# ArduIRv2.net
KiCad netlist of a schematic drawn in EAGLE
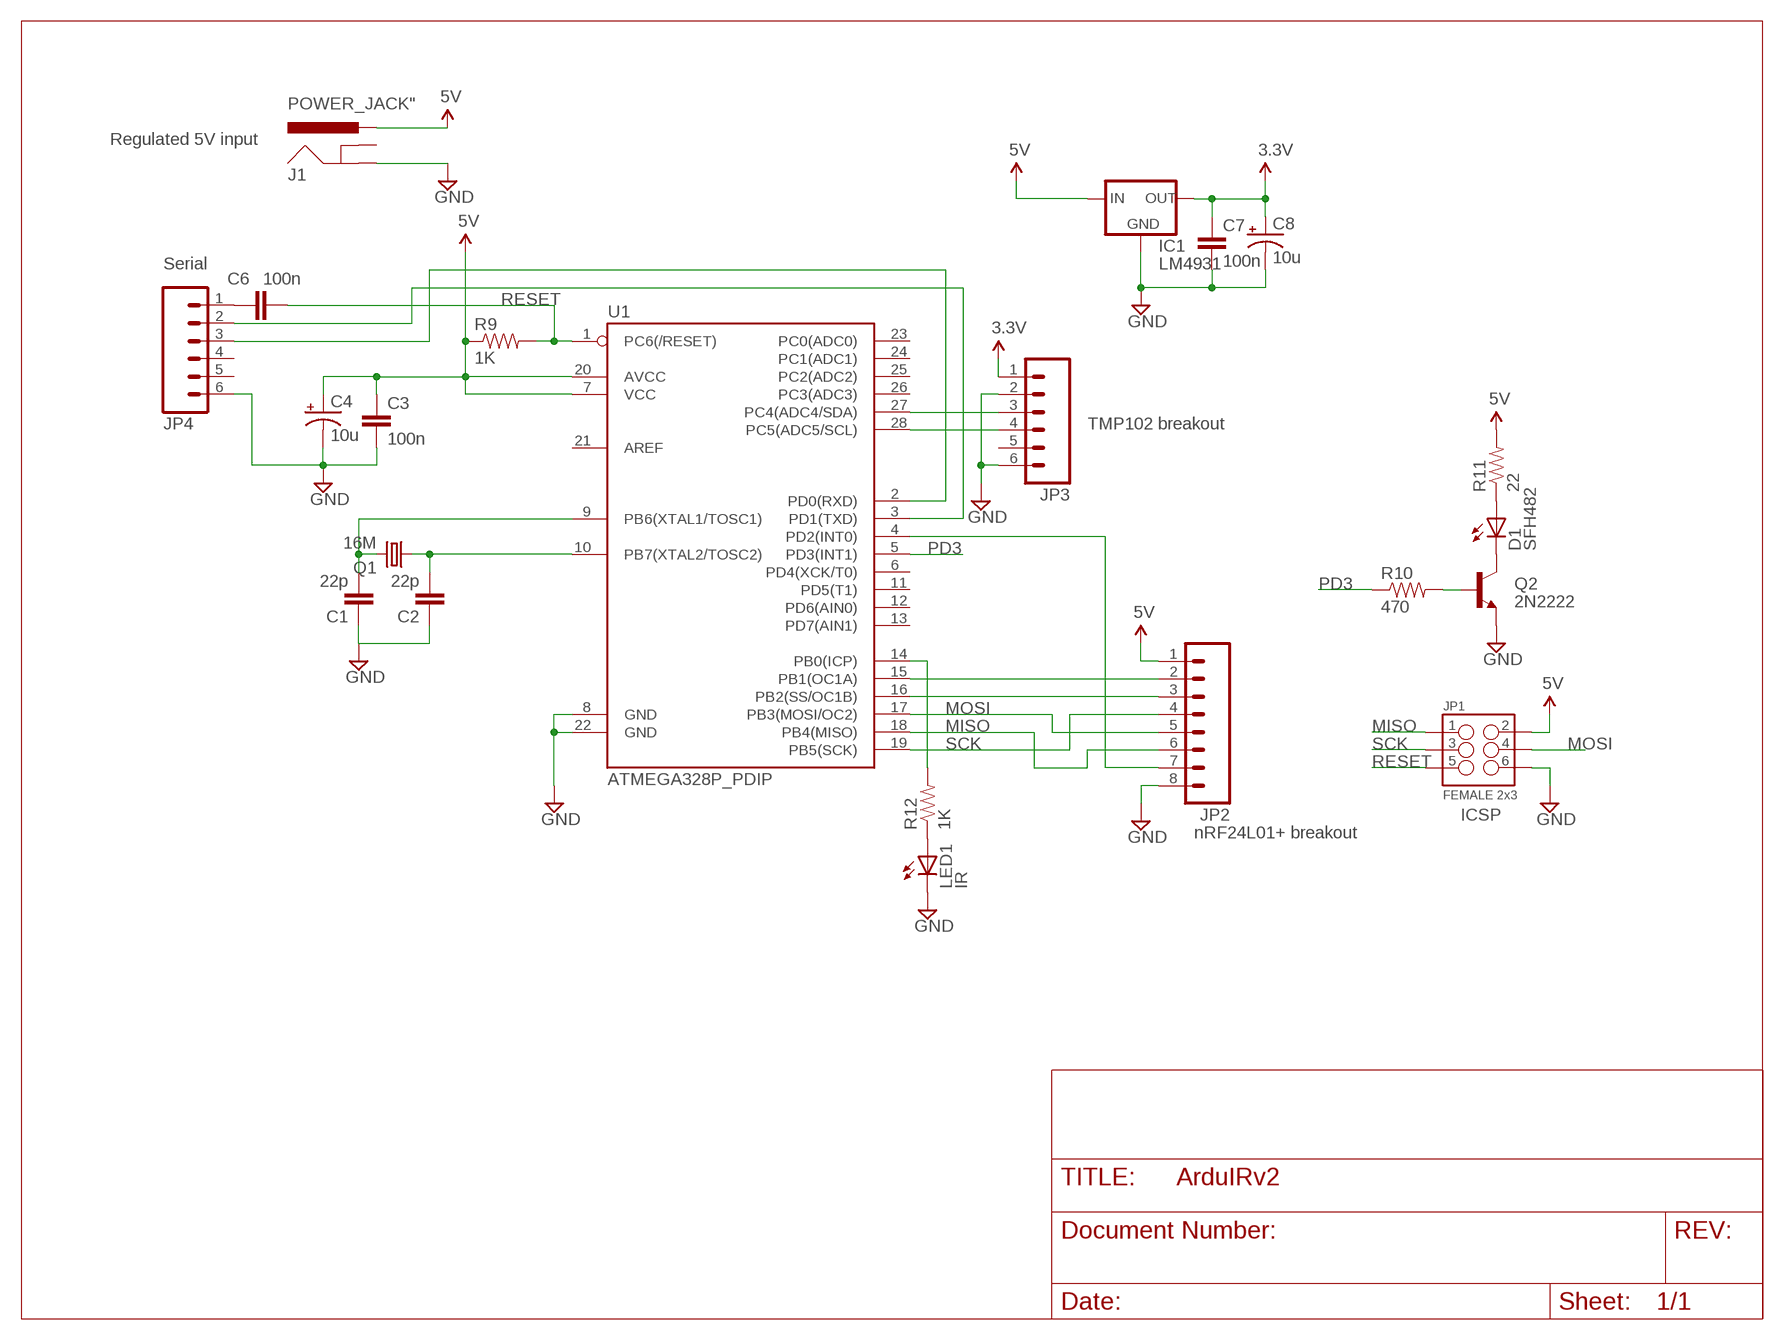
[diagram p0: schematic, sheet 1]

(export (version "E")
  (design (tool "Eeschema 10.0.6"))
  (components
    (comp (ref "C1")
      (value "22p")
      (footprint "eagle-import:CAP-PTH-SMALL")
      (libsource (lib "eagle-import") (part "CAPPTH"))
    )
    (comp (ref "C2")
      (value "22p")
      (footprint "eagle-import:CAP-PTH-SMALL")
      (libsource (lib "eagle-import") (part "CAPPTH"))
    )
    (comp (ref "C3")
      (value "100n")
      (footprint "eagle-import:CAP-PTH-SMALL-KIT")
      (libsource (lib "eagle-import") (part "0.1UF-50V-20%(PTH)KIT-EZ"))
    )
    (comp (ref "C4")
      (value "10u")
      (footprint "eagle-import:CPOL-RADIAL-10UF-25V")
      (libsource (lib "eagle-import") (part "CAP_POLPTH2"))
    )
    (comp (ref "C6")
      (value "100n")
      (footprint "eagle-import:CAP-PTH-SMALL-KIT")
      (libsource (lib "eagle-import") (part "0.1UF-50V-20%(PTH)KIT-EZ"))
    )
    (comp (ref "C7")
      (value "100n")
      (footprint "eagle-import:CAP-PTH-SMALL-KIT")
      (libsource (lib "eagle-import") (part "0.1UF-50V-20%(PTH)KIT-EZ"))
    )
    (comp (ref "C8")
      (value "10u")
      (footprint "eagle-import:CPOL-RADIAL-10UF-25V")
      (libsource (lib "eagle-import") (part "CAP_POLPTH2"))
    )
    (comp (ref "D1")
      (value "SFH482")
      (footprint "eagle-import:SFH482")
      (libsource (lib "eagle-import") (part "SFH482"))
    )
    (comp (ref "IC1")
      (value "LM4931")
      (footprint "eagle-import:L4931_REGULATOR")
      (libsource (lib "eagle-import") (part "REGULATORTO220"))
    )
    (comp (ref "J1")
      (value "POWER_JACK\"")
      (footprint "eagle-import:POWER_JACK")
      (libsource (lib "eagle-import") (part "POWER_JACK{dblquote}"))
    )
    (comp (ref "JP1")
      (value "FEMALE 2x3")
      (footprint "eagle-import:2X3-SHROUDED")
      (libsource (lib "eagle-import") (part "M03X2SHROUD"))
    )
    (comp (ref "JP2")
      (value "M08SILK_FEMALE_PTH")
      (footprint "eagle-import:1X08")
      (libsource (lib "eagle-import") (part "M08SILK_FEMALE_PTH"))
    )
    (comp (ref "JP3")
      (value "M06SILK_FEMALE_PTH")
      (footprint "eagle-import:1X06")
      (libsource (lib "eagle-import") (part "M06SILK_FEMALE_PTH"))
    )
    (comp (ref "JP4")
      (value "M06SILK_FEMALE_PTH")
      (footprint "eagle-import:1X06")
      (libsource (lib "eagle-import") (part "M06SILK_FEMALE_PTH"))
    )
    (comp (ref "LED1")
      (value "IR")
      (footprint "eagle-import:LED5MM")
      (libsource (lib "eagle-import") (part "LED5MM"))
    )
    (comp (ref "Q1")
      (value "16M")
      (footprint "eagle-import:HC49US")
      (libsource (lib "eagle-import") (part "CRYSTALHC49US"))
    )
    (comp (ref "Q2")
      (value "2N2222")
      (footprint "eagle-import:TO-92-AMMO")
      (libsource (lib "eagle-import") (part "TRANSISTOR_NPNTO-92-AMMO"))
    )
    (comp (ref "R9")
      (value "1K")
      (footprint "eagle-import:AXIAL-0.1EZ")
      (libsource (lib "eagle-import") (part "1KOHM-1/4W-1%(PTH)VERT-KIT"))
    )
    (comp (ref "R10")
      (value "470")
      (footprint "eagle-import:AXIAL-0.1EZ")
      (libsource (lib "eagle-import") (part "1KOHM-1/4W-1%(PTH)VERT-KIT"))
    )
    (comp (ref "R11")
      (value "22")
      (footprint "eagle-import:AXIAL-0.1EZ")
      (libsource (lib "eagle-import") (part "1KOHM-1/4W-1%(PTH)VERT-KIT"))
    )
    (comp (ref "R12")
      (value "1K")
      (footprint "eagle-import:AXIAL-0.1EZ")
      (libsource (lib "eagle-import") (part "10KOHM-1/4W-1%(PTH)VERT-KIT"))
    )
    (comp (ref "U1")
      (value "ATMEGA328P_PDIP")
      (footprint "eagle-import:DIL28-3")
      (libsource (lib "eagle-import") (part "ATMEGA328P_PDIP"))
    )
  )
  (nets
    (net (code "1") (name "/MISO") (class "Default")
      (node (ref "JP1") (pin "1") (pinfunction "1_1") (pintype "bidirectional"))
      (node (ref "JP2") (pin "6") (pinfunction "6_6") (pintype "passive"))
      (node (ref "U1") (pin "18") (pinfunction "PB4(MISO)_18") (pintype "bidirectional"))
    )
    (net (code "2") (name "/MOSI") (class "Default")
      (node (ref "JP1") (pin "4") (pinfunction "4_4") (pintype "bidirectional"))
      (node (ref "JP2") (pin "5") (pinfunction "5_5") (pintype "passive"))
      (node (ref "U1") (pin "17") (pinfunction "PB3(MOSI/OC2)_17") (pintype "bidirectional"))
    )
    (net (code "3") (name "/PD3") (class "Default")
      (node (ref "R10") (pin "P$1") (pinfunction "1_P$1") (pintype "passive"))
      (node (ref "U1") (pin "5") (pinfunction "PD3(INT1)_5") (pintype "bidirectional"))
    )
    (net (code "4") (name "/RESET") (class "Default")
      (node (ref "C6") (pin "1") (pinfunction "1_1") (pintype "passive"))
      (node (ref "JP1") (pin "5") (pinfunction "5_5") (pintype "bidirectional"))
      (node (ref "R9") (pin "P$2") (pinfunction "2_P$2") (pintype "passive"))
      (node (ref "U1") (pin "1") (pinfunction "PC6(/RESET)_1") (pintype "bidirectional"))
    )
    (net (code "5") (name "/SCK") (class "Default")
      (node (ref "JP1") (pin "3") (pinfunction "3_3") (pintype "bidirectional"))
      (node (ref "JP2") (pin "4") (pinfunction "4_4") (pintype "passive"))
      (node (ref "U1") (pin "19") (pinfunction "PB5(SCK)_19") (pintype "bidirectional"))
    )
    (net (code "6") (name "3.3V") (class "Default")
      (node (ref "C7") (pin "1") (pinfunction "1_1") (pintype "passive"))
      (node (ref "C8") (pin "1") (pinfunction "+_1") (pintype "passive"))
      (node (ref "IC1") (pin "OUT") (pinfunction "OUT_OUT") (pintype "passive"))
      (node (ref "JP3") (pin "1") (pinfunction "1_1") (pintype "passive"))
    )
    (net (code "7") (name "5V") (class "Default")
      (node (ref "C3") (pin "1") (pinfunction "1_1") (pintype "passive"))
      (node (ref "C4") (pin "1") (pinfunction "+_1") (pintype "passive"))
      (node (ref "IC1") (pin "IN") (pinfunction "IN_IN") (pintype "input"))
      (node (ref "J1") (pin "PWR") (pinfunction "PWR_PWR") (pintype "bidirectional"))
      (node (ref "JP1") (pin "2") (pinfunction "2_2") (pintype "bidirectional"))
      (node (ref "JP2") (pin "1") (pinfunction "1_1") (pintype "passive"))
      (node (ref "R11") (pin "P$2") (pinfunction "2_P$2") (pintype "passive"))
      (node (ref "R9") (pin "P$1") (pinfunction "1_P$1") (pintype "passive"))
      (node (ref "U1") (pin "20") (pinfunction "AVCC_20") (pintype "bidirectional"))
      (node (ref "U1") (pin "7") (pinfunction "VCC_7") (pintype "bidirectional"))
    )
    (net (code "8") (name "GND") (class "Default")
      (node (ref "C1") (pin "1") (pinfunction "1_1") (pintype "passive"))
      (node (ref "C2") (pin "1") (pinfunction "1_1") (pintype "passive"))
      (node (ref "C3") (pin "2") (pinfunction "2_2") (pintype "passive"))
      (node (ref "C4") (pin "2") (pinfunction "-_2") (pintype "passive"))
      (node (ref "C7") (pin "2") (pinfunction "2_2") (pintype "passive"))
      (node (ref "C8") (pin "2") (pinfunction "-_2") (pintype "passive"))
      (node (ref "IC1") (pin "GND") (pinfunction "GND_GND") (pintype "input"))
      (node (ref "J1") (pin "GND") (pinfunction "GND_GND") (pintype "bidirectional"))
      (node (ref "JP1") (pin "6") (pinfunction "6_6") (pintype "bidirectional"))
      (node (ref "JP2") (pin "8") (pinfunction "8_8") (pintype "passive"))
      (node (ref "JP3") (pin "2") (pinfunction "2_2") (pintype "passive"))
      (node (ref "JP3") (pin "6") (pinfunction "6_6") (pintype "passive"))
      (node (ref "JP4") (pin "6") (pinfunction "6_6") (pintype "passive"))
      (node (ref "LED1") (pin "K") (pinfunction "C_K") (pintype "passive"))
      (node (ref "Q2") (pin "1") (pinfunction "E_1") (pintype "passive"))
      (node (ref "U1") (pin "22") (pinfunction "GND_22") (pintype "bidirectional"))
      (node (ref "U1") (pin "8") (pinfunction "GND_8") (pintype "bidirectional"))
    )
    (net (code "9") (name "Net-(C6-Pad2)") (class "Default")
      (node (ref "C6") (pin "2") (pinfunction "2_2") (pintype "passive"))
      (node (ref "JP4") (pin "1") (pinfunction "1_1") (pintype "passive"))
    )
    (net (code "10") (name "Net-(D1-C)") (class "Default")
      (node (ref "D1") (pin "K") (pinfunction "C_K") (pintype "passive"))
      (node (ref "Q2") (pin "3") (pinfunction "C_3") (pintype "passive"))
    )
    (net (code "11") (name "Net-(Q2-B)") (class "Default")
      (node (ref "Q2") (pin "2") (pinfunction "B_2") (pintype "passive"))
      (node (ref "R10") (pin "P$2") (pinfunction "2_P$2") (pintype "passive"))
    )
    (net (code "12") (name "Net-(R11-1)") (class "Default")
      (node (ref "D1") (pin "A") (pinfunction "A_A") (pintype "passive"))
      (node (ref "R11") (pin "P$1") (pinfunction "1_P$1") (pintype "passive"))
    )
    (net (code "13") (name "Net-(R12-1)") (class "Default")
      (node (ref "LED1") (pin "A") (pinfunction "A_A") (pintype "passive"))
      (node (ref "R12") (pin "P$1") (pinfunction "1_P$1") (pintype "passive"))
    )
    (net (code "14") (name "Net-(R12-2)") (class "Default")
      (node (ref "R12") (pin "P$2") (pinfunction "2_P$2") (pintype "passive"))
      (node (ref "U1") (pin "14") (pinfunction "PB0(ICP)_14") (pintype "bidirectional"))
    )
    (net (code "15") (name "Net-(U1-PB1(OC1A))") (class "Default")
      (node (ref "JP2") (pin "2") (pinfunction "2_2") (pintype "passive"))
      (node (ref "U1") (pin "15") (pinfunction "PB1(OC1A)_15") (pintype "bidirectional"))
    )
    (net (code "16") (name "Net-(U1-PB2(SS{slash}OC1B))") (class "Default")
      (node (ref "JP2") (pin "3") (pinfunction "3_3") (pintype "passive"))
      (node (ref "U1") (pin "16") (pinfunction "PB2(SS/OC1B)_16") (pintype "bidirectional"))
    )
    (net (code "17") (name "Net-(U1-PB6(XTAL1{slash}TOSC1))") (class "Default")
      (node (ref "C1") (pin "2") (pinfunction "2_2") (pintype "passive"))
      (node (ref "Q1") (pin "2") (pinfunction "2_2") (pintype "passive"))
      (node (ref "U1") (pin "9") (pinfunction "PB6(XTAL1/TOSC1)_9") (pintype "bidirectional"))
    )
    (net (code "18") (name "Net-(U1-PB7(XTAL2{slash}TOSC2))") (class "Default")
      (node (ref "C2") (pin "2") (pinfunction "2_2") (pintype "passive"))
      (node (ref "Q1") (pin "1") (pinfunction "1_1") (pintype "passive"))
      (node (ref "U1") (pin "10") (pinfunction "PB7(XTAL2/TOSC2)_10") (pintype "bidirectional"))
    )
    (net (code "19") (name "Net-(U1-PC4(ADC4{slash}SDA))") (class "Default")
      (node (ref "JP3") (pin "3") (pinfunction "3_3") (pintype "passive"))
      (node (ref "U1") (pin "27") (pinfunction "PC4(ADC4/SDA)_27") (pintype "bidirectional"))
    )
    (net (code "20") (name "Net-(U1-PC5(ADC5{slash}SCL))") (class "Default")
      (node (ref "JP3") (pin "4") (pinfunction "4_4") (pintype "passive"))
      (node (ref "U1") (pin "28") (pinfunction "PC5(ADC5/SCL)_28") (pintype "bidirectional"))
    )
    (net (code "21") (name "Net-(U1-PD0(RXD))") (class "Default")
      (node (ref "JP4") (pin "3") (pinfunction "3_3") (pintype "passive"))
      (node (ref "U1") (pin "2") (pinfunction "PD0(RXD)_2") (pintype "bidirectional"))
    )
    (net (code "22") (name "Net-(U1-PD1(TXD))") (class "Default")
      (node (ref "JP4") (pin "2") (pinfunction "2_2") (pintype "passive"))
      (node (ref "U1") (pin "3") (pinfunction "PD1(TXD)_3") (pintype "bidirectional"))
    )
    (net (code "23") (name "Net-(U1-PD2(INT0))") (class "Default")
      (node (ref "JP2") (pin "7") (pinfunction "7_7") (pintype "passive"))
      (node (ref "U1") (pin "4") (pinfunction "PD2(INT0)_4") (pintype "bidirectional"))
    )
    (net (code "24") (name "unconnected-(J1-PadGNDBREAK)") (class "Default")
      (node (ref "J1") (pin "GNDBREAK") (pinfunction "GNDBREAK_GNDBREAK") (pintype "bidirectional"))
    )
    (net (code "25") (name "unconnected-(JP3-Pad5)") (class "Default")
      (node (ref "JP3") (pin "5") (pinfunction "5_5") (pintype "passive"))
    )
    (net (code "26") (name "unconnected-(JP4-Pad4)") (class "Default")
      (node (ref "JP4") (pin "4") (pinfunction "4_4") (pintype "passive"))
    )
    (net (code "27") (name "unconnected-(JP4-Pad5)") (class "Default")
      (node (ref "JP4") (pin "5") (pinfunction "5_5") (pintype "passive"))
    )
    (net (code "28") (name "unconnected-(U1-AREF-Pad21)") (class "Default")
      (node (ref "U1") (pin "21") (pinfunction "AREF_21") (pintype "bidirectional"))
    )
    (net (code "29") (name "unconnected-(U1-PC0(ADC0)-Pad23)") (class "Default")
      (node (ref "U1") (pin "23") (pinfunction "PC0(ADC0)_23") (pintype "bidirectional"))
    )
    (net (code "30") (name "unconnected-(U1-PC1(ADC1)-Pad24)") (class "Default")
      (node (ref "U1") (pin "24") (pinfunction "PC1(ADC1)_24") (pintype "bidirectional"))
    )
    (net (code "31") (name "unconnected-(U1-PC2(ADC2)-Pad25)") (class "Default")
      (node (ref "U1") (pin "25") (pinfunction "PC2(ADC2)_25") (pintype "bidirectional"))
    )
    (net (code "32") (name "unconnected-(U1-PC3(ADC3)-Pad26)") (class "Default")
      (node (ref "U1") (pin "26") (pinfunction "PC3(ADC3)_26") (pintype "bidirectional"))
    )
    (net (code "33") (name "unconnected-(U1-PD4(XCK{slash}T0)-Pad6)") (class "Default")
      (node (ref "U1") (pin "6") (pinfunction "PD4(XCK/T0)_6") (pintype "bidirectional"))
    )
    (net (code "34") (name "unconnected-(U1-PD5(T1)-Pad11)") (class "Default")
      (node (ref "U1") (pin "11") (pinfunction "PD5(T1)_11") (pintype "bidirectional"))
    )
    (net (code "35") (name "unconnected-(U1-PD6(AIN0)-Pad12)") (class "Default")
      (node (ref "U1") (pin "12") (pinfunction "PD6(AIN0)_12") (pintype "bidirectional"))
    )
    (net (code "36") (name "unconnected-(U1-PD7(AIN1)-Pad13)") (class "Default")
      (node (ref "U1") (pin "13") (pinfunction "PD7(AIN1)_13") (pintype "bidirectional"))
    )
  )
)
